# Schematic.net
KiCad netlist of a schematic drawn in EAGLE
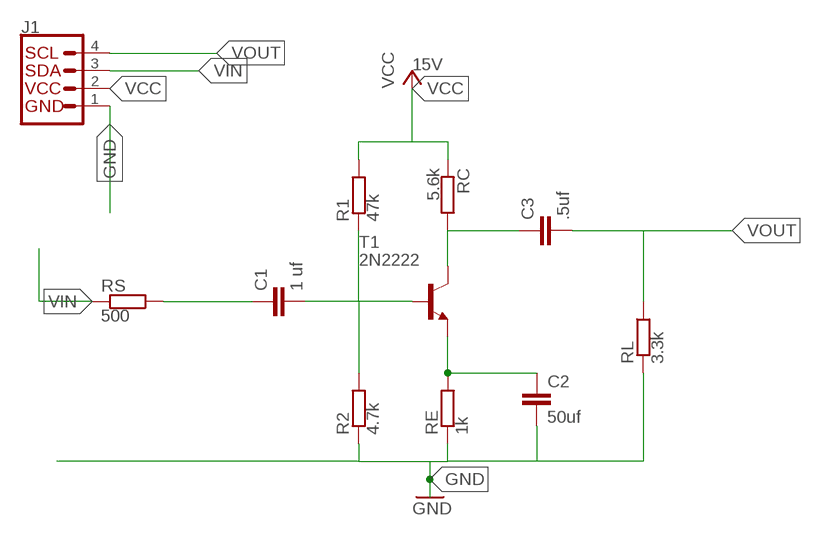
[diagram p0: schematic, sheet 1]

(export (version "E")
  (design (tool "Eeschema 10.0.6"))
  (components
    (comp (ref "C1")
      (value "1 uf")
      (footprint "eagle-import:C2.5-3")
      (libsource (lib "eagle-import") (part "C2,5-3"))
    )
    (comp (ref "C2")
      (value "50uf")
      (footprint "eagle-import:C2.5-3")
      (libsource (lib "eagle-import") (part "C2,5-3"))
    )
    (comp (ref "C3")
      (value ".5uf")
      (footprint "eagle-import:C2.5-3")
      (libsource (lib "eagle-import") (part "C2,5-3"))
    )
    (comp (ref "J1")
      (value "QWIIC_CONNECTORJS-1MM")
      (footprint "eagle-import:1X04_1MM_RA")
      (libsource (lib "eagle-import") (part "QWIIC_CONNECTORJS-1MM"))
    )
    (comp (ref "R1")
      (value "47k")
      (footprint "eagle-import:BVS")
      (libsource (lib "eagle-import") (part "BVS"))
    )
    (comp (ref "R2")
      (value "4.7k")
      (footprint "eagle-import:BVS")
      (libsource (lib "eagle-import") (part "BVS"))
    )
    (comp (ref "RC")
      (value "5.6k")
      (footprint "eagle-import:BVS")
      (libsource (lib "eagle-import") (part "BVS"))
    )
    (comp (ref "RE")
      (value "1k")
      (footprint "eagle-import:BVS")
      (libsource (lib "eagle-import") (part "BVS"))
    )
    (comp (ref "RL")
      (value "3.3k")
      (footprint "eagle-import:BVS")
      (libsource (lib "eagle-import") (part "BVS"))
    )
    (comp (ref "RS")
      (value "500")
      (footprint "eagle-import:BVS")
      (libsource (lib "eagle-import") (part "BVS"))
    )
    (comp (ref "T1")
      (value "2N2222")
      (footprint "eagle-import:TO18")
      (libsource (lib "eagle-import") (part "2N2222"))
    )
  )
  (nets
    (net (code "1") (name "/2") (class "Default")
      (node (ref "J1") (pin "2") (pinfunction "2_2") (pintype "power_in"))
    )
    (net (code "2") (name "GND") (class "Default")
      (node (ref "C2") (pin "2") (pinfunction "2_2") (pintype "passive"))
      (node (ref "J1") (pin "1") (pinfunction "1_1") (pintype "power_in"))
      (node (ref "R2") (pin "2") (pinfunction "2_2") (pintype "passive"))
      (node (ref "RE") (pin "2") (pinfunction "2_2") (pintype "passive"))
      (node (ref "RL") (pin "2") (pinfunction "2_2") (pintype "passive"))
    )
    (net (code "3") (name "Net-(C1-Pad1)") (class "Default")
      (node (ref "C1") (pin "1") (pinfunction "1_1") (pintype "passive"))
      (node (ref "RS") (pin "1") (pinfunction "1_1") (pintype "passive"))
    )
    (net (code "4") (name "Net-(T1-B)") (class "Default")
      (node (ref "C1") (pin "2") (pinfunction "2_2") (pintype "passive"))
      (node (ref "R1") (pin "2") (pinfunction "2_2") (pintype "passive"))
      (node (ref "R2") (pin "1") (pinfunction "1_1") (pintype "passive"))
      (node (ref "T1") (pin "2") (pinfunction "B_2") (pintype "passive"))
    )
    (net (code "5") (name "Net-(T1-C)") (class "Default")
      (node (ref "C3") (pin "1") (pinfunction "1_1") (pintype "passive"))
      (node (ref "RC") (pin "1") (pinfunction "1_1") (pintype "passive"))
      (node (ref "T1") (pin "3") (pinfunction "C_3") (pintype "passive"))
    )
    (net (code "6") (name "Net-(T1-E)") (class "Default")
      (node (ref "C2") (pin "1") (pinfunction "1_1") (pintype "passive"))
      (node (ref "RE") (pin "1") (pinfunction "1_1") (pintype "passive"))
      (node (ref "T1") (pin "1") (pinfunction "E_1") (pintype "passive"))
    )
    (net (code "7") (name "VCC") (class "Default")
      (node (ref "R1") (pin "1") (pinfunction "1_1") (pintype "passive"))
      (node (ref "RC") (pin "2") (pinfunction "2_2") (pintype "passive"))
    )
    (net (code "8") (name "VIN") (class "Default")
      (node (ref "J1") (pin "3") (pinfunction "3_3") (pintype "passive"))
      (node (ref "RS") (pin "2") (pinfunction "2_2") (pintype "passive"))
    )
    (net (code "9") (name "VOUT") (class "Default")
      (node (ref "C3") (pin "2") (pinfunction "2_2") (pintype "passive"))
      (node (ref "J1") (pin "4") (pinfunction "4_4") (pintype "passive"))
      (node (ref "RL") (pin "1") (pinfunction "1_1") (pintype "passive"))
    )
  )
)
